# XT60_Bus.net
KiCad netlist of a schematic drawn in Altium Designer
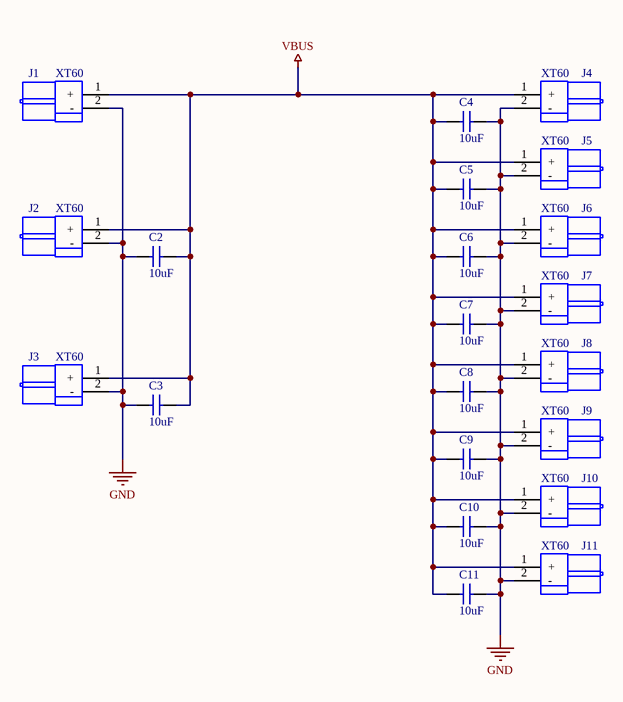
[diagram p0: XT60_Bus.SchDoc]

(export (version "E")
  (design (tool "Eeschema 10.0.6"))
  (components
    (comp (ref "C2")
      (value "10uF")
      (footprint "1210_Capacitor")
      (description "CAP CER 10UF 50V 10% X5R 1210")
      (fields
        (field (name "MANUFACTURER") "Taiyo Yuden")
        (field (name "Comment") "C_1210_10uF")
        (field (name "SVP CREATOR") "Matt Rogge")
      )
      (libsource (lib "capacitor") (part "C_1210_10uF"))
    )
    (comp (ref "C3")
      (value "10uF")
      (footprint "1210_Capacitor")
      (description "CAP CER 10UF 50V 10% X5R 1210")
      (fields
        (field (name "MANUFACTURER") "Taiyo Yuden")
        (field (name "Comment") "C_1210_10uF")
        (field (name "SVP CREATOR") "Matt Rogge")
      )
      (libsource (lib "capacitor") (part "C_1210_10uF"))
    )
    (comp (ref "C4")
      (value "10uF")
      (footprint "1210_Capacitor")
      (description "CAP CER 10UF 50V 10% X5R 1210")
      (fields
        (field (name "MANUFACTURER") "Taiyo Yuden")
        (field (name "Comment") "C_1210_10uF")
        (field (name "SVP CREATOR") "Matt Rogge")
      )
      (libsource (lib "capacitor") (part "C_1210_10uF"))
    )
    (comp (ref "C5")
      (value "10uF")
      (footprint "1210_Capacitor")
      (description "CAP CER 10UF 50V 10% X5R 1210")
      (fields
        (field (name "MANUFACTURER") "Taiyo Yuden")
        (field (name "Comment") "C_1210_10uF")
        (field (name "SVP CREATOR") "Matt Rogge")
      )
      (libsource (lib "capacitor") (part "C_1210_10uF"))
    )
    (comp (ref "C6")
      (value "10uF")
      (footprint "1210_Capacitor")
      (description "CAP CER 10UF 50V 10% X5R 1210")
      (fields
        (field (name "MANUFACTURER") "Taiyo Yuden")
        (field (name "Comment") "C_1210_10uF")
        (field (name "SVP CREATOR") "Matt Rogge")
      )
      (libsource (lib "capacitor") (part "C_1210_10uF"))
    )
    (comp (ref "C7")
      (value "10uF")
      (footprint "1210_Capacitor")
      (description "CAP CER 10UF 50V 10% X5R 1210")
      (fields
        (field (name "MANUFACTURER") "Taiyo Yuden")
        (field (name "Comment") "C_1210_10uF")
        (field (name "SVP CREATOR") "Matt Rogge")
      )
      (libsource (lib "capacitor") (part "C_1210_10uF"))
    )
    (comp (ref "C8")
      (value "10uF")
      (footprint "1210_Capacitor")
      (description "CAP CER 10UF 50V 10% X5R 1210")
      (fields
        (field (name "MANUFACTURER") "Taiyo Yuden")
        (field (name "Comment") "C_1210_10uF")
        (field (name "SVP CREATOR") "Matt Rogge")
      )
      (libsource (lib "capacitor") (part "C_1210_10uF"))
    )
    (comp (ref "C9")
      (value "10uF")
      (footprint "1210_Capacitor")
      (description "CAP CER 10UF 50V 10% X5R 1210")
      (fields
        (field (name "MANUFACTURER") "Taiyo Yuden")
        (field (name "Comment") "C_1210_10uF")
        (field (name "SVP CREATOR") "Matt Rogge")
      )
      (libsource (lib "capacitor") (part "C_1210_10uF"))
    )
    (comp (ref "C10")
      (value "10uF")
      (footprint "1210_Capacitor")
      (description "CAP CER 10UF 50V 10% X5R 1210")
      (fields
        (field (name "MANUFACTURER") "Taiyo Yuden")
        (field (name "Comment") "C_1210_10uF")
        (field (name "SVP CREATOR") "Matt Rogge")
      )
      (libsource (lib "capacitor") (part "C_1210_10uF"))
    )
    (comp (ref "C11")
      (value "10uF")
      (footprint "1210_Capacitor")
      (description "CAP CER 10UF 50V 10% X5R 1210")
      (fields
        (field (name "MANUFACTURER") "Taiyo Yuden")
        (field (name "Comment") "C_1210_10uF")
        (field (name "SVP CREATOR") "Matt Rogge")
      )
      (libsource (lib "capacitor") (part "C_1210_10uF"))
    )
    (comp (ref "J1")
      (value "XT60")
      (footprint "J_XT60_Thru_Female")
      (description "60 Amp XT60 Connector")
      (libsource (lib "connector") (part "J_XT60"))
    )
    (comp (ref "J2")
      (value "XT60")
      (footprint "J_XT60_Thru_Female")
      (description "60 Amp XT60 Connector")
      (libsource (lib "connector") (part "J_XT60"))
    )
    (comp (ref "J3")
      (value "XT60")
      (footprint "J_XT60_Thru_Female")
      (description "60 Amp XT60 Connector")
      (libsource (lib "connector") (part "J_XT60"))
    )
    (comp (ref "J4")
      (value "XT60")
      (footprint "J_XT60_Thru_Male")
      (description "60 Amp XT60 Connector")
      (libsource (lib "connector") (part "J_XT60"))
    )
    (comp (ref "J5")
      (value "XT60")
      (footprint "J_XT60_Thru_Male")
      (description "60 Amp XT60 Connector")
      (libsource (lib "connector") (part "J_XT60"))
    )
    (comp (ref "J6")
      (value "XT60")
      (footprint "J_XT60_Thru_Male")
      (description "60 Amp XT60 Connector")
      (libsource (lib "connector") (part "J_XT60"))
    )
    (comp (ref "J7")
      (value "XT60")
      (footprint "J_XT60_Thru_Male")
      (description "60 Amp XT60 Connector")
      (libsource (lib "connector") (part "J_XT60"))
    )
    (comp (ref "J8")
      (value "XT60")
      (footprint "J_XT60_Thru_Male")
      (description "60 Amp XT60 Connector")
      (libsource (lib "connector") (part "J_XT60"))
    )
    (comp (ref "J9")
      (value "XT60")
      (footprint "J_XT60_Thru_Male")
      (description "60 Amp XT60 Connector")
      (libsource (lib "connector") (part "J_XT60"))
    )
    (comp (ref "J10")
      (value "XT60")
      (footprint "J_XT60_Thru_Male")
      (description "60 Amp XT60 Connector")
      (libsource (lib "connector") (part "J_XT60"))
    )
    (comp (ref "J11")
      (value "XT60")
      (footprint "J_XT60_Thru_Male")
      (description "60 Amp XT60 Connector")
      (libsource (lib "connector") (part "J_XT60"))
    )
  )
  (nets
    (net (code "1") (name "GND") (class "Default")
      (node (ref "C10") (pin "2") (pinfunction "2_2") (pintype "passive"))
      (node (ref "C11") (pin "2") (pinfunction "2_2") (pintype "passive"))
      (node (ref "C2") (pin "1") (pinfunction "1_1") (pintype "passive"))
      (node (ref "C3") (pin "1") (pinfunction "1_1") (pintype "passive"))
      (node (ref "C4") (pin "2") (pinfunction "2_2") (pintype "passive"))
      (node (ref "C5") (pin "2") (pinfunction "2_2") (pintype "passive"))
      (node (ref "C6") (pin "2") (pinfunction "2_2") (pintype "passive"))
      (node (ref "C7") (pin "2") (pinfunction "2_2") (pintype "passive"))
      (node (ref "C8") (pin "2") (pinfunction "2_2") (pintype "passive"))
      (node (ref "C9") (pin "2") (pinfunction "2_2") (pintype "passive"))
      (node (ref "J1") (pin "2") (pinfunction "-_2") (pintype "passive"))
      (node (ref "J10") (pin "2") (pinfunction "-_2") (pintype "passive"))
      (node (ref "J11") (pin "2") (pinfunction "-_2") (pintype "passive"))
      (node (ref "J2") (pin "2") (pinfunction "-_2") (pintype "passive"))
      (node (ref "J3") (pin "2") (pinfunction "-_2") (pintype "passive"))
      (node (ref "J4") (pin "2") (pinfunction "-_2") (pintype "passive"))
      (node (ref "J5") (pin "2") (pinfunction "-_2") (pintype "passive"))
      (node (ref "J6") (pin "2") (pinfunction "-_2") (pintype "passive"))
      (node (ref "J7") (pin "2") (pinfunction "-_2") (pintype "passive"))
      (node (ref "J8") (pin "2") (pinfunction "-_2") (pintype "passive"))
      (node (ref "J9") (pin "2") (pinfunction "-_2") (pintype "passive"))
    )
    (net (code "2") (name "VBUS") (class "Default")
      (node (ref "C10") (pin "1") (pinfunction "1_1") (pintype "passive"))
      (node (ref "C11") (pin "1") (pinfunction "1_1") (pintype "passive"))
      (node (ref "C2") (pin "2") (pinfunction "2_2") (pintype "passive"))
      (node (ref "C3") (pin "2") (pinfunction "2_2") (pintype "passive"))
      (node (ref "C4") (pin "1") (pinfunction "1_1") (pintype "passive"))
      (node (ref "C5") (pin "1") (pinfunction "1_1") (pintype "passive"))
      (node (ref "C6") (pin "1") (pinfunction "1_1") (pintype "passive"))
      (node (ref "C7") (pin "1") (pinfunction "1_1") (pintype "passive"))
      (node (ref "C8") (pin "1") (pinfunction "1_1") (pintype "passive"))
      (node (ref "C9") (pin "1") (pinfunction "1_1") (pintype "passive"))
      (node (ref "J1") (pin "1") (pinfunction "+_1") (pintype "passive"))
      (node (ref "J10") (pin "1") (pinfunction "+_1") (pintype "passive"))
      (node (ref "J11") (pin "1") (pinfunction "+_1") (pintype "passive"))
      (node (ref "J2") (pin "1") (pinfunction "+_1") (pintype "passive"))
      (node (ref "J3") (pin "1") (pinfunction "+_1") (pintype "passive"))
      (node (ref "J4") (pin "1") (pinfunction "+_1") (pintype "passive"))
      (node (ref "J5") (pin "1") (pinfunction "+_1") (pintype "passive"))
      (node (ref "J6") (pin "1") (pinfunction "+_1") (pintype "passive"))
      (node (ref "J7") (pin "1") (pinfunction "+_1") (pintype "passive"))
      (node (ref "J8") (pin "1") (pinfunction "+_1") (pintype "passive"))
      (node (ref "J9") (pin "1") (pinfunction "+_1") (pintype "passive"))
    )
  )
)
